# ANALOG_VOUTPUT.net
KiCad netlist of a schematic drawn in Altium Designer
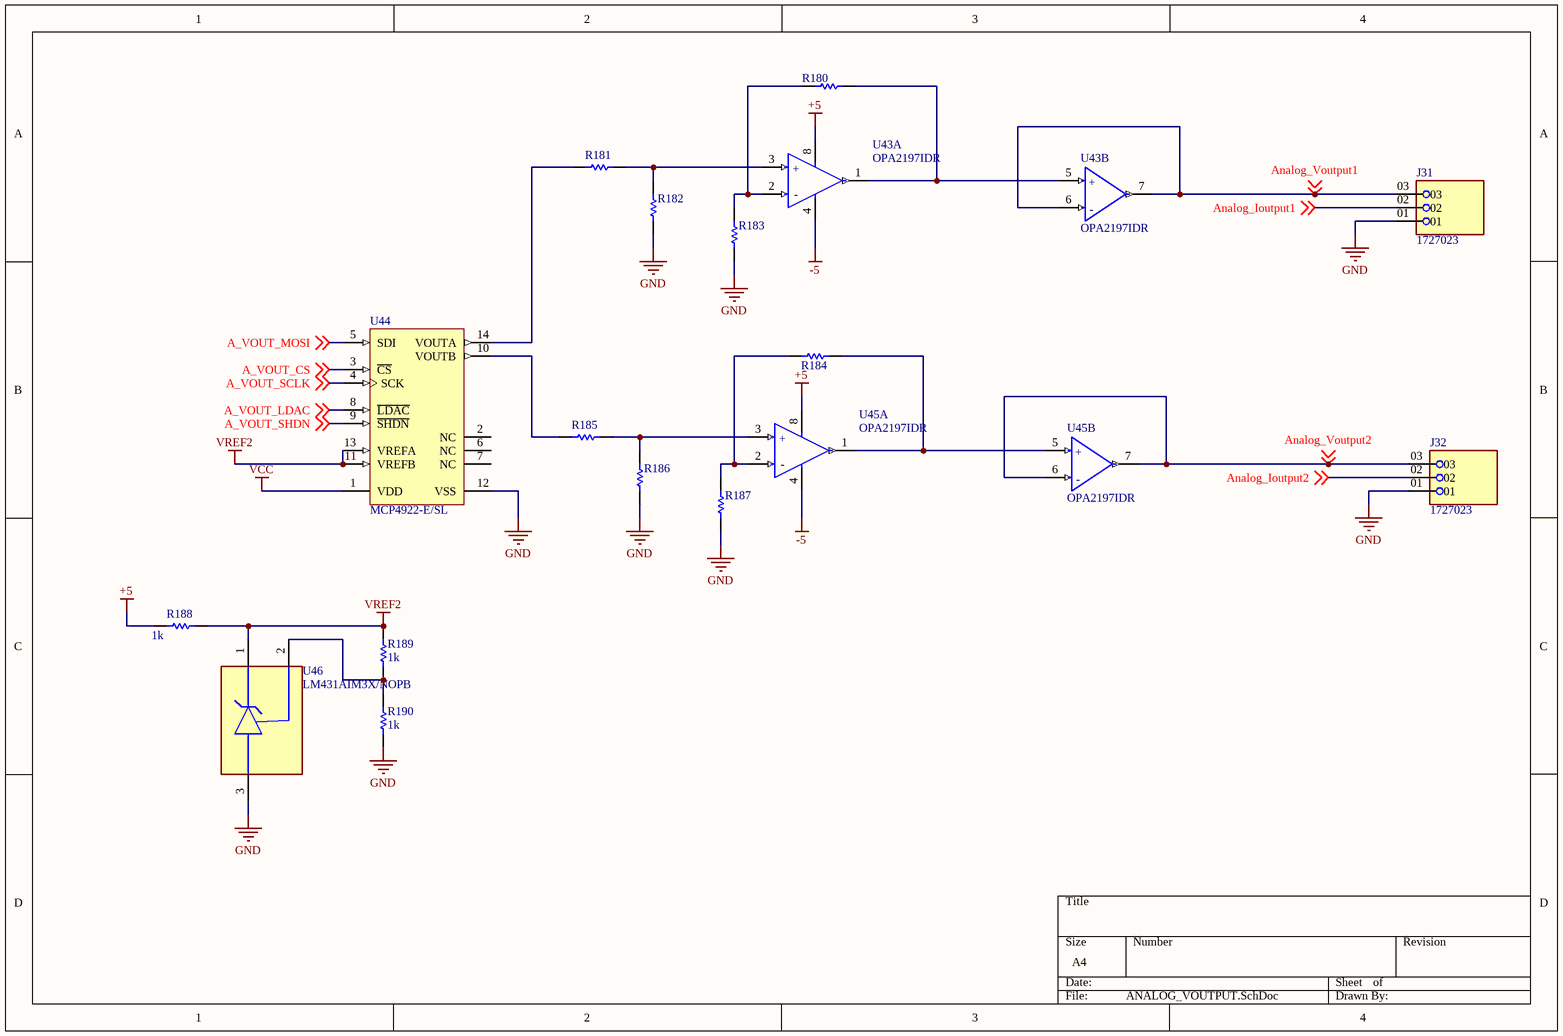
[diagram p0: ANALOG_VOUTPUT.SchDoc]

(export (version "E")
  (design (tool "Eeschema 10.0.6"))
  (components
    (comp (ref "J31")
      (value "1727023")
      (footprint "PHOENIX_1727023")
      (fields (field (name "MF") "Phoenix Contact"))
      (libsource (lib "1727023") (part "1727023"))
    )
    (comp (ref "J32")
      (value "1727023")
      (footprint "PHOENIX_1727023")
      (fields (field (name "MF") "Phoenix Contact"))
      (libsource (lib "1727023") (part "1727023"))
    )
    (comp (ref "R180")
      (value "CRCW060310K0FKEA")
      (footprint "RESC1609X50X30NL8T20")
      (description "Chip Resistor, 10 KOhm, +/- 1%, 100 mW, -55 to 155 degC, 0603 (1608 Metric), RoHS, Tape and Reel")
      (fields (field (name "MANUFACTURER") "Vishay Semiconductor"))
      (libsource (lib "Altium Content Vault") (part "RES-2"))
    )
    (comp (ref "R181")
      (value "CRCW060310K0FKEA")
      (footprint "RESC1609X50X30NL8T20")
      (description "Chip Resistor, 10 KOhm, +/- 1%, 100 mW, -55 to 155 degC, 0603 (1608 Metric), RoHS, Tape and Reel")
      (fields (field (name "MANUFACTURER") "Vishay Semiconductor"))
      (libsource (lib "Altium Content Vault") (part "RES-2"))
    )
    (comp (ref "R182")
      (value "CRCW060310K0FKEA")
      (footprint "RESC1609X50X30NL8T20")
      (description "Chip Resistor, 10 KOhm, +/- 1%, 100 mW, -55 to 155 degC, 0603 (1608 Metric), RoHS, Tape and Reel")
      (fields (field (name "MANUFACTURER") "Vishay Semiconductor"))
      (libsource (lib "Altium Content Vault") (part "RES-2"))
    )
    (comp (ref "R183")
      (value "CRCW060310K0FKEA")
      (footprint "RESC1609X50X30NL8T20")
      (description "Chip Resistor, 10 KOhm, +/- 1%, 100 mW, -55 to 155 degC, 0603 (1608 Metric), RoHS, Tape and Reel")
      (fields (field (name "MANUFACTURER") "Vishay Semiconductor"))
      (libsource (lib "Altium Content Vault") (part "RES-2"))
    )
    (comp (ref "R184")
      (value "CRCW060310K0FKEA")
      (footprint "RESC1609X50X30NL8T20")
      (description "Chip Resistor, 10 KOhm, +/- 1%, 100 mW, -55 to 155 degC, 0603 (1608 Metric), RoHS, Tape and Reel")
      (fields (field (name "MANUFACTURER") "Vishay Semiconductor"))
      (libsource (lib "Altium Content Vault") (part "RES-2"))
    )
    (comp (ref "R185")
      (value "CRCW060310K0FKEA")
      (footprint "RESC1609X50X30NL8T20")
      (description "Chip Resistor, 10 KOhm, +/- 1%, 100 mW, -55 to 155 degC, 0603 (1608 Metric), RoHS, Tape and Reel")
      (fields (field (name "MANUFACTURER") "Vishay Semiconductor"))
      (libsource (lib "Altium Content Vault") (part "RES-2"))
    )
    (comp (ref "R186")
      (value "CRCW060310K0FKEA")
      (footprint "RESC1609X50X30NL8T20")
      (description "Chip Resistor, 10 KOhm, +/- 1%, 100 mW, -55 to 155 degC, 0603 (1608 Metric), RoHS, Tape and Reel")
      (fields (field (name "MANUFACTURER") "Vishay Semiconductor"))
      (libsource (lib "Altium Content Vault") (part "RES-2"))
    )
    (comp (ref "R187")
      (value "CRCW060310K0FKEA")
      (footprint "RESC1609X50X30NL8T20")
      (description "Chip Resistor, 10 KOhm, +/- 1%, 100 mW, -55 to 155 degC, 0603 (1608 Metric), RoHS, Tape and Reel")
      (fields (field (name "MANUFACTURER") "Vishay Semiconductor"))
      (libsource (lib "Altium Content Vault") (part "RES-2"))
    )
    (comp (ref "R188")
      (value "1k")
      (footprint "RESC2013X50X30NL20T20")
      (fields (field (name "MANUFACTURER") "Vishay Dale") (field (name "PART NUMBER") "CRCW08051K00FKTC"))
      (libsource (lib "Altium Content Vault") (part "RES"))
    )
    (comp (ref "R189")
      (value "1k")
      (footprint "RESC2013X50X30NL20T20")
      (fields (field (name "MANUFACTURER") "Vishay Dale") (field (name "PART NUMBER") "CRCW08051K00FKTC"))
      (libsource (lib "Altium Content Vault") (part "RES"))
    )
    (comp (ref "R190")
      (value "1k")
      (footprint "RESC2013X50X30NL20T20")
      (fields (field (name "MANUFACTURER") "Vishay Dale") (field (name "PART NUMBER") "CRCW08051K00FKTC"))
      (libsource (lib "Altium Content Vault") (part "RES"))
    )
    (comp (ref "U43")
      (value "OPA2197IDR")
      (footprint "FP-D0008A-MFG")
      (description "IC OP AMP GP RR 10MHZ 8-SOIC")
      (fields
        (field (name "MANUFACTURER") "Texas Instruments")
        (field (name "OCTOPART") "https://octopart.com/opa2197idr-texas+instruments-75179702")
      )
      (libsource (lib "Altium Content Vault") (part "499df5fc91ff7ad023bcaf249d8becd"))
    )
    (comp (ref "U44")
      (value "MCP4922-E/SL")
      (footprint "SOIC-SL14_M")
      (description "12-Bit DAC with SPI Interface, 14-Pin SOIC 150mil, Extended Temperature")
      (libsource (lib "Altium Content Vault") (part "CON-DAC-MCP4922-14"))
    )
    (comp (ref "U45")
      (value "OPA2197IDR")
      (footprint "FP-D0008A-MFG")
      (description "IC OP AMP GP RR 10MHZ 8-SOIC")
      (fields
        (field (name "MANUFACTURER") "Texas Instruments")
        (field (name "OCTOPART") "https://octopart.com/opa2197idr-texas+instruments-75179702")
      )
      (libsource (lib "Altium Content Vault") (part "499df5fc91ff7ad023bcaf249d8becd"))
    )
    (comp (ref "U46")
      (value "LM431AIM3X/NOPB")
      (footprint "FP-DBZ0003A-IPC_B")
      (description "IC VREF SHUNT 37V 2.2% SOT23-3")
      (fields (field (name "TOLERANCE") "2%"))
      (libsource (lib "Altium Content Vault") (part "493a0447014da16a84e61b4a2bbdac0"))
    )
  )
  (nets
    (net (code "1") (name "+5") (class "Default")
      (node (ref "R188") (pin "1") (pinfunction "1_1") (pintype "passive"))
      (node (ref "U43") (pin "8") (pinfunction "V+_8") (pintype "power_in"))
      (node (ref "U45") (pin "8") (pinfunction "V+_8") (pintype "power_in"))
    )
    (net (code "2") (name "-5") (class "Default")
      (node (ref "U43") (pin "4") (pinfunction "V-_4") (pintype "power_in"))
      (node (ref "U45") (pin "4") (pinfunction "V-_4") (pintype "power_in"))
    )
    (net (code "3") (name "A_VOUT_CS") (class "Default")
      (node (ref "U44") (pin "3") (pinfunction "~{CS}_3") (pintype "input"))
    )
    (net (code "4") (name "A_VOUT_LDAC") (class "Default")
      (node (ref "U44") (pin "8") (pinfunction "~{LDAC}_8") (pintype "input"))
    )
    (net (code "5") (name "A_VOUT_MOSI") (class "Default")
      (node (ref "U44") (pin "5") (pinfunction "SDI_5") (pintype "input"))
    )
    (net (code "6") (name "A_VOUT_SCLK") (class "Default")
      (node (ref "U44") (pin "4") (pinfunction "SCK_4") (pintype "input"))
    )
    (net (code "7") (name "A_VOUT_SHDN") (class "Default")
      (node (ref "U44") (pin "9") (pinfunction "~{SHDN}_9") (pintype "input"))
    )
    (net (code "8") (name "Analog_Ioutput1") (class "Default")
      (node (ref "J31") (pin "02") (pinfunction "02_02") (pintype "passive"))
    )
    (net (code "9") (name "Analog_Ioutput2") (class "Default")
      (node (ref "J32") (pin "02") (pinfunction "02_02") (pintype "passive"))
    )
    (net (code "10") (name "Analog_Voutput1") (class "Default")
      (node (ref "J31") (pin "03") (pinfunction "03_03") (pintype "passive"))
      (node (ref "U43") (pin "6") (pinfunction "-IN_B_6") (pintype "input"))
      (node (ref "U43") (pin "7") (pinfunction "OUT_B_7") (pintype "output"))
    )
    (net (code "11") (name "Analog_Voutput2") (class "Default")
      (node (ref "J32") (pin "03") (pinfunction "03_03") (pintype "passive"))
      (node (ref "U45") (pin "6") (pinfunction "-IN_B_6") (pintype "input"))
      (node (ref "U45") (pin "7") (pinfunction "OUT_B_7") (pintype "output"))
    )
    (net (code "12") (name "GND") (class "Default")
      (node (ref "J31") (pin "01") (pinfunction "01_01") (pintype "passive"))
      (node (ref "J32") (pin "01") (pinfunction "01_01") (pintype "passive"))
      (node (ref "R182") (pin "1") (pinfunction "1_1") (pintype "passive"))
      (node (ref "R183") (pin "1") (pinfunction "1_1") (pintype "passive"))
      (node (ref "R186") (pin "1") (pinfunction "1_1") (pintype "passive"))
      (node (ref "R187") (pin "1") (pinfunction "1_1") (pintype "passive"))
      (node (ref "R190") (pin "1") (pinfunction "1_1") (pintype "passive"))
      (node (ref "U44") (pin "12") (pinfunction "VSS_12") (pintype "power_in"))
      (node (ref "U46") (pin "3") (pinfunction "A_3") (pintype "passive"))
    )
    (net (code "13") (name "Net-(U43A-+IN_A)") (class "Default")
      (node (ref "R181") (pin "2") (pinfunction "2_2") (pintype "passive"))
      (node (ref "R182") (pin "2") (pinfunction "2_2") (pintype "passive"))
      (node (ref "U43") (pin "3") (pinfunction "+IN_A_3") (pintype "input"))
    )
    (net (code "14") (name "Net-(U43A--IN_A)") (class "Default")
      (node (ref "R180") (pin "2") (pinfunction "2_2") (pintype "passive"))
      (node (ref "R183") (pin "2") (pinfunction "2_2") (pintype "passive"))
      (node (ref "U43") (pin "2") (pinfunction "-IN_A_2") (pintype "input"))
    )
    (net (code "15") (name "Net-(U43A-OUT_A)") (class "Default")
      (node (ref "R180") (pin "1") (pinfunction "1_1") (pintype "passive"))
      (node (ref "U43") (pin "1") (pinfunction "OUT_A_1") (pintype "output"))
      (node (ref "U43") (pin "5") (pinfunction "+IN_B_5") (pintype "input"))
    )
    (net (code "16") (name "Net-(U44-VOUTA)") (class "Default")
      (node (ref "R181") (pin "1") (pinfunction "1_1") (pintype "passive"))
      (node (ref "U44") (pin "14") (pinfunction "VOUTA_14") (pintype "output"))
    )
    (net (code "17") (name "Net-(U44-VOUTB)") (class "Default")
      (node (ref "R185") (pin "1") (pinfunction "1_1") (pintype "passive"))
      (node (ref "U44") (pin "10") (pinfunction "VOUTB_10") (pintype "output"))
    )
    (net (code "18") (name "Net-(U45A-+IN_A)") (class "Default")
      (node (ref "R185") (pin "2") (pinfunction "2_2") (pintype "passive"))
      (node (ref "R186") (pin "2") (pinfunction "2_2") (pintype "passive"))
      (node (ref "U45") (pin "3") (pinfunction "+IN_A_3") (pintype "input"))
    )
    (net (code "19") (name "Net-(U45A--IN_A)") (class "Default")
      (node (ref "R184") (pin "2") (pinfunction "2_2") (pintype "passive"))
      (node (ref "R187") (pin "2") (pinfunction "2_2") (pintype "passive"))
      (node (ref "U45") (pin "2") (pinfunction "-IN_A_2") (pintype "input"))
    )
    (net (code "20") (name "Net-(U45A-OUT_A)") (class "Default")
      (node (ref "R184") (pin "1") (pinfunction "1_1") (pintype "passive"))
      (node (ref "U45") (pin "1") (pinfunction "OUT_A_1") (pintype "output"))
      (node (ref "U45") (pin "5") (pinfunction "+IN_B_5") (pintype "input"))
    )
    (net (code "21") (name "Net-(U46-REF)") (class "Default")
      (node (ref "R189") (pin "1") (pinfunction "1_1") (pintype "passive"))
      (node (ref "R190") (pin "2") (pinfunction "2_2") (pintype "passive"))
      (node (ref "U46") (pin "2") (pinfunction "REF_2") (pintype "passive"))
    )
    (net (code "22") (name "VCC") (class "Default")
      (node (ref "U44") (pin "1") (pinfunction "VDD_1") (pintype "power_in"))
    )
    (net (code "23") (name "VREF2") (class "Default")
      (node (ref "R188") (pin "2") (pinfunction "2_2") (pintype "passive"))
      (node (ref "R189") (pin "2") (pinfunction "2_2") (pintype "passive"))
      (node (ref "U44") (pin "11") (pinfunction "VREFB_11") (pintype "input"))
      (node (ref "U44") (pin "13") (pinfunction "VREFA_13") (pintype "input"))
      (node (ref "U46") (pin "1") (pinfunction "C_1") (pintype "passive"))
    )
    (net (code "24") (name "unconnected-(U44-NC-Pad2)") (class "Default")
      (node (ref "U44") (pin "2") (pinfunction "NC_2") (pintype "passive"))
    )
    (net (code "25") (name "unconnected-(U44-NC-Pad6)") (class "Default")
      (node (ref "U44") (pin "6") (pinfunction "NC_6") (pintype "passive"))
    )
    (net (code "26") (name "unconnected-(U44-NC-Pad7)") (class "Default")
      (node (ref "U44") (pin "7") (pinfunction "NC_7") (pintype "passive"))
    )
  )
)
